# 03__EFR32_Signal_Assignments.net
KiCad netlist of a schematic drawn in Altium Designer
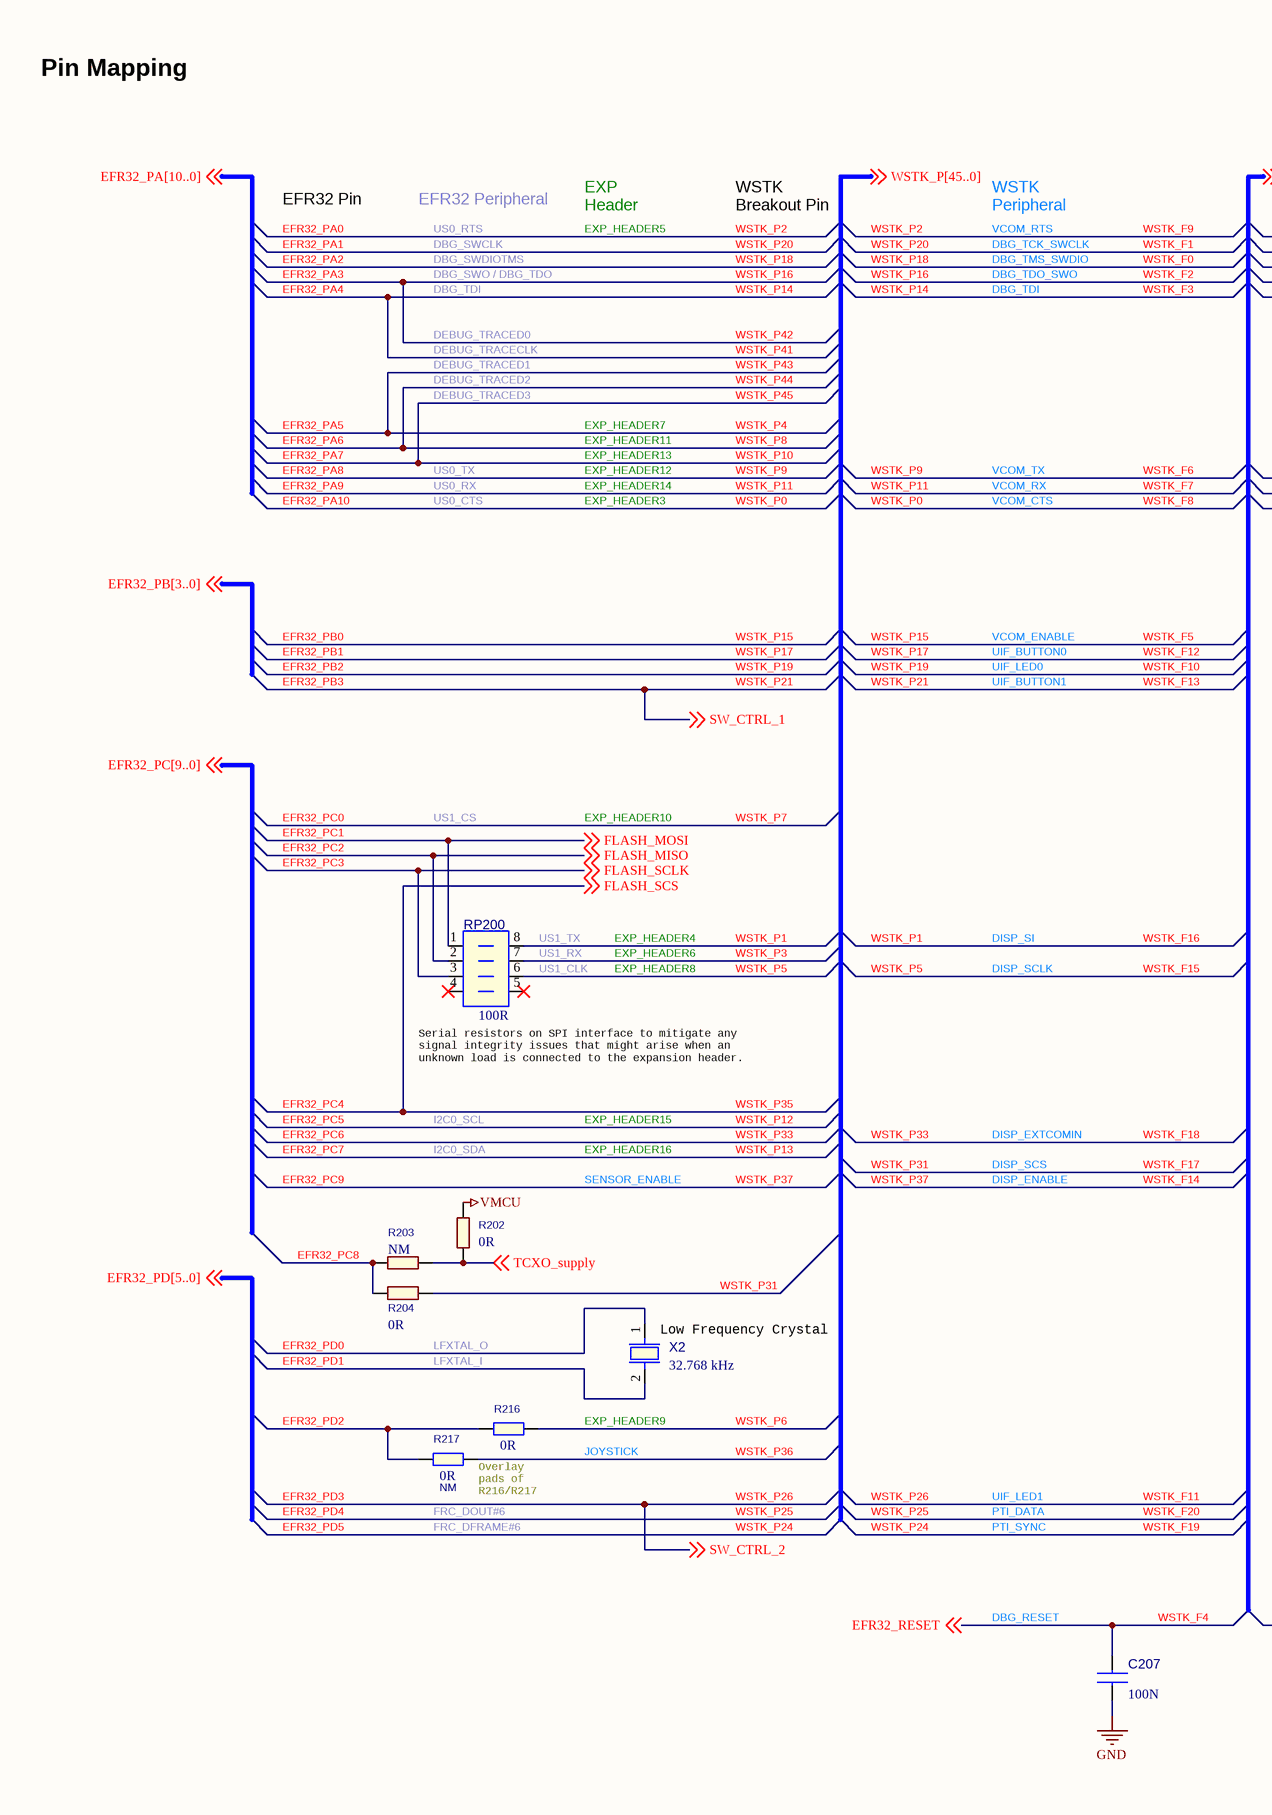
[diagram p0: 03_ EFR32 Signal Assignments.SchDoc, left]
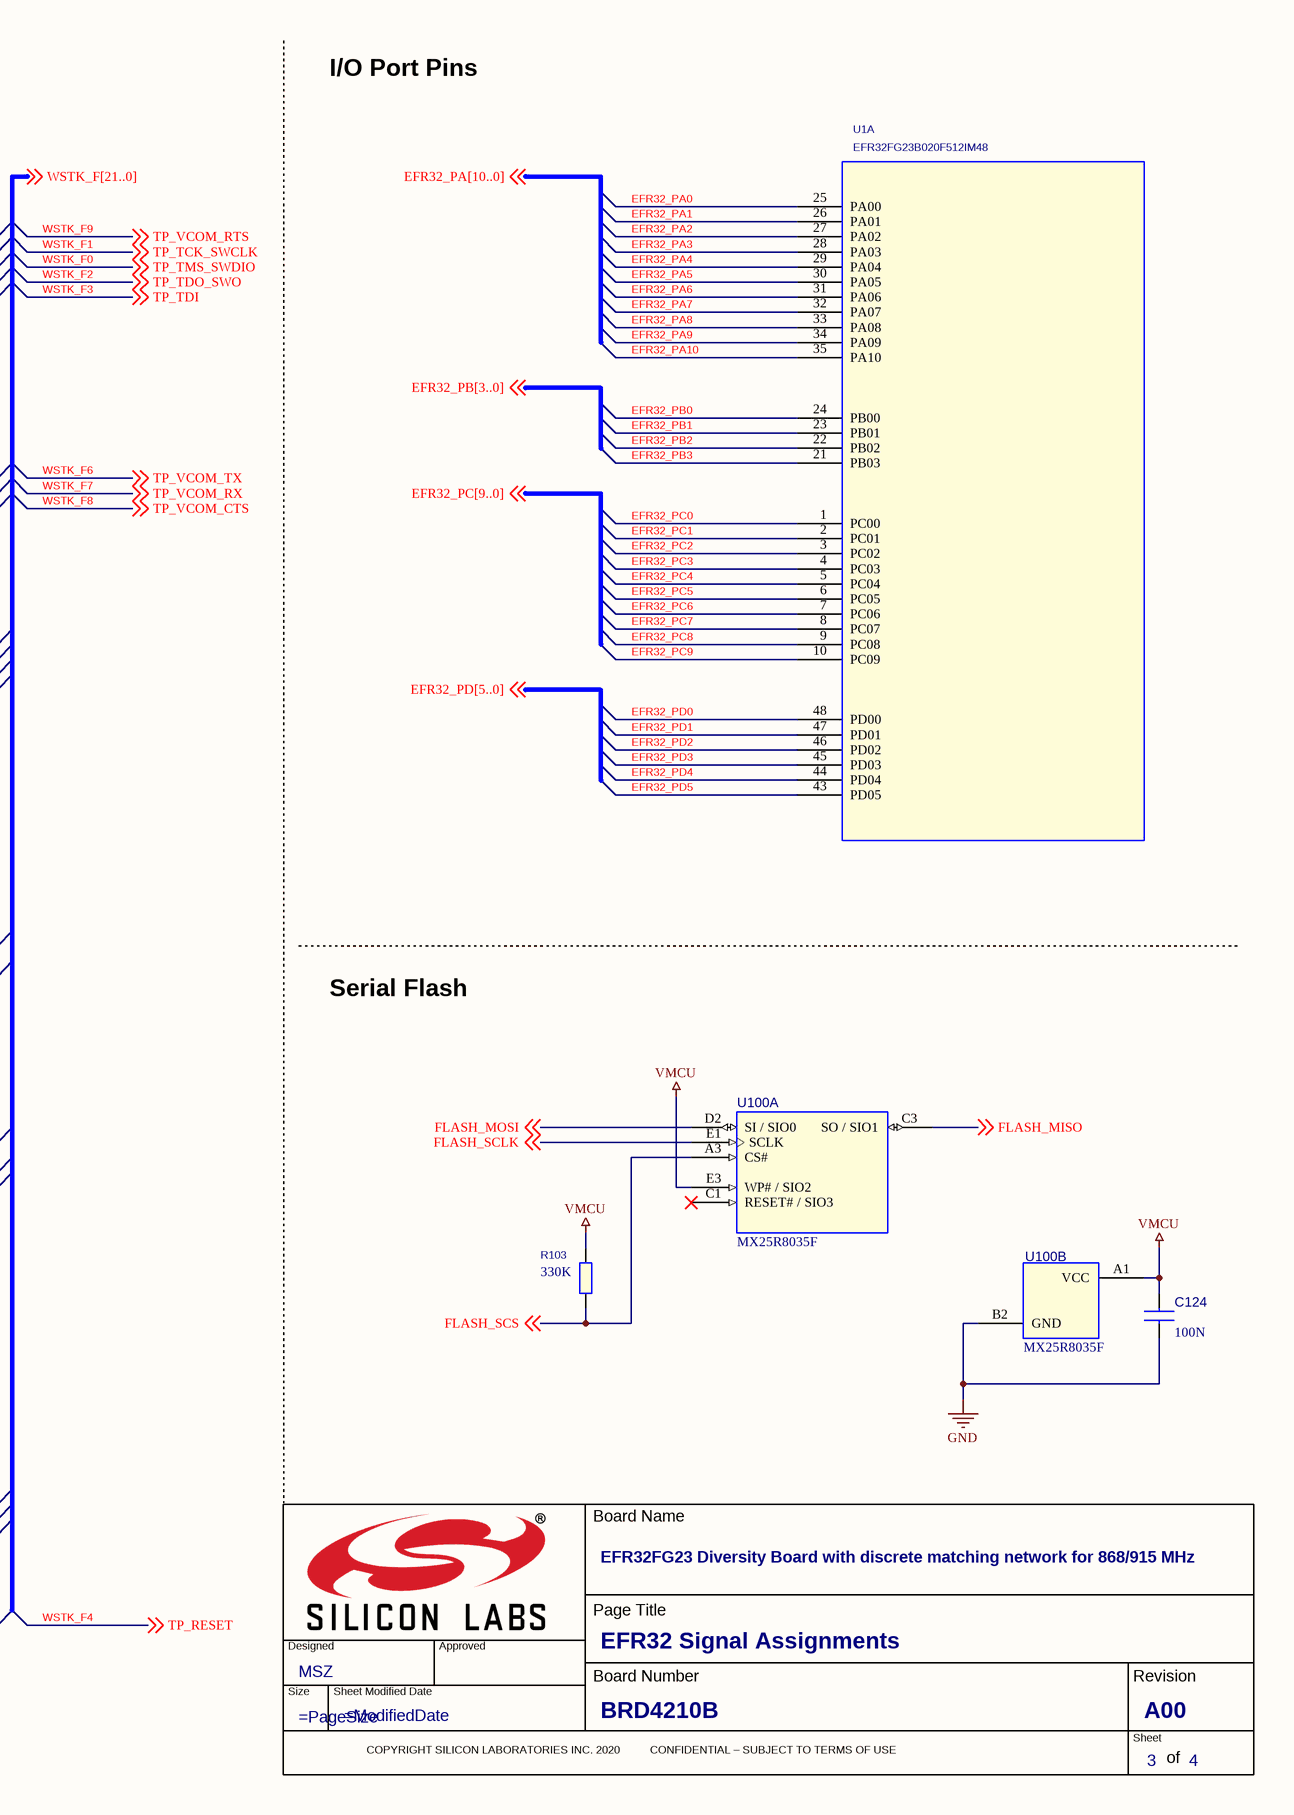
[diagram p1: 03_ EFR32 Signal Assignments.SchDoc, right]

(export (version "E")
  (design (tool "Eeschema 10.0.6"))
  (components
    (comp (ref "C124")
      (value "100N")
      (footprint "C0201_L")
      (fields (field (name "TOLERANCE") "20%"))
      (libsource (lib "*") (part "C0201"))
    )
    (comp (ref "C207")
      (value "100N")
      (footprint "C0201_L")
      (fields (field (name "TOLERANCE") "20%"))
      (libsource (lib "*") (part "C0201"))
    )
    (comp (ref "R103") (value "330K") (footprint "R0201_L") (libsource (lib "*") (part "R0201")))
    (comp (ref "R202") (value "0R") (footprint "R0201_L") (libsource (lib "") (part "R0201_1")))
    (comp (ref "R203") (value "NM") (footprint "R0201_L") (libsource (lib "BRD4210A_Library") (part "R0201")))
    (comp (ref "R204") (value "0R") (footprint "R0201_L") (libsource (lib "BRD4210A_Library") (part "R0201")))
    (comp (ref "R216") (value "0R") (footprint "R0402_L") (libsource (lib "*") (part "R0402")))
    (comp (ref "R217")
      (value "0R")
      (footprint "R0402_L")
      (fields (field (name "NOT MOUNTED") "NM"))
      (libsource (lib "*") (part "R0402"))
    )
    (comp (ref "RP200")
      (value "100R")
      (footprint "RES_MNR04-8")
      (fields (field (name "MFG") "ROHM"))
      (libsource (lib "*") (part "MNR04M0APJ101"))
    )
    (comp (ref "U1")
      (value "EFR32FG23B020F512IM48")
      (footprint "QFN48_M040_6.0X6.0_EP_SL")
      (fields (field (name "MFG") "Silicon Labs"))
      (libsource (lib "*") (part "EFR32xG23_QFN48"))
    )
    (comp (ref "U100")
      (value "MX25R8035F")
      (footprint "BGA8_M040_1.24x1.75_WLCSP")
      (fields (field (name "MFG") "Macronix"))
      (libsource (lib "*") (part "MX25R8035"))
    )
    (comp (ref "X2")
      (value "32.768 kHz")
      (footprint "X_MCS_CM8V-T1A")
      (fields (field (name "MFG") "Micro Crystal AG"))
      (libsource (lib "*") (part "CM8V-T1A"))
    )
  )
  (nets
    (net (code "3") (name "EFR32_PC8") (class "Default")
      (node (ref "R203") (pin "2") (pinfunction "2_2") (pintype "passive"))
      (node (ref "R204") (pin "2") (pinfunction "2_2") (pintype "passive"))
      (node (ref "U1") (pin "9") (pinfunction "PC08_9") (pintype "passive"))
    )
    (net (code "5") (name "EFR32_PD0") (class "Default")
      (node (ref "U1") (pin "48") (pinfunction "PD00_48") (pintype "passive"))
      (node (ref "X2") (pin "1") (pinfunction "1_1") (pintype "passive"))
    )
    (net (code "6") (name "EFR32_PD1") (class "Default")
      (node (ref "U1") (pin "47") (pinfunction "PD01_47") (pintype "passive"))
      (node (ref "X2") (pin "2") (pinfunction "2_2") (pintype "passive"))
    )
    (net (code "7") (name "EFR32_PD2") (class "Default")
      (node (ref "R216") (pin "1") (pinfunction "1_1") (pintype "passive"))
      (node (ref "R217") (pin "1") (pinfunction "1_1") (pintype "passive"))
      (node (ref "U1") (pin "46") (pinfunction "PD02_46") (pintype "passive"))
    )
    (net (code "9") (name "EFR32_RESET") (class "Default")
      (node (ref "C207") (pin "1") (pinfunction "1_1") (pintype "passive"))
    )
    (net (code "10") (name "FLASH_MISO") (class "Default")
      (node (ref "RP200") (pin "2") (pinfunction "R12_2") (pintype "passive"))
      (node (ref "U1") (pin "3") (pinfunction "PC02_3") (pintype "passive"))
      (node (ref "U100") (pin "C3") (pinfunction "SO_/_SIO1_C3") (pintype "bidirectional"))
    )
    (net (code "11") (name "FLASH_MOSI") (class "Default")
      (node (ref "RP200") (pin "1") (pinfunction "R11_1") (pintype "passive"))
      (node (ref "U1") (pin "2") (pinfunction "PC01_2") (pintype "passive"))
      (node (ref "U100") (pin "D2") (pinfunction "SI_/_SIO0_D2") (pintype "bidirectional"))
    )
    (net (code "12") (name "FLASH_SCLK") (class "Default")
      (node (ref "RP200") (pin "3") (pinfunction "R13_3") (pintype "passive"))
      (node (ref "U1") (pin "4") (pinfunction "PC03_4") (pintype "passive"))
      (node (ref "U100") (pin "E1") (pinfunction "SCLK_E1") (pintype "input"))
    )
    (net (code "13") (name "FLASH_SCS") (class "Default")
      (node (ref "R103") (pin "1") (pinfunction "1_1") (pintype "passive"))
      (node (ref "U1") (pin "5") (pinfunction "PC04_5") (pintype "passive"))
      (node (ref "U100") (pin "A3") (pinfunction "CS#_A3") (pintype "input"))
    )
    (net (code "14") (name "GND") (class "Default")
      (node (ref "C124") (pin "2") (pinfunction "2_2") (pintype "passive"))
      (node (ref "C207") (pin "2") (pinfunction "2_2") (pintype "passive"))
      (node (ref "U100") (pin "B2") (pinfunction "GND_B2") (pintype "power_in"))
    )
    (net (code "15") (name "SW_CTRL_1") (class "Default")
      (node (ref "U1") (pin "21") (pinfunction "PB03_21") (pintype "passive"))
    )
    (net (code "16") (name "SW_CTRL_2") (class "Default")
      (node (ref "U1") (pin "45") (pinfunction "PD03_45") (pintype "passive"))
    )
    (net (code "17") (name "TCXO_supply") (class "Default")
      (node (ref "R202") (pin "1") (pinfunction "1_1") (pintype "passive"))
      (node (ref "R203") (pin "1") (pinfunction "1_1") (pintype "passive"))
    )
    (net (code "18") (name "TP_TCK_SWCLK") (class "Default")
      (node (ref "U1") (pin "26") (pinfunction "PA01_26") (pintype "passive"))
    )
    (net (code "19") (name "TP_TDI") (class "Default")
      (node (ref "U1") (pin "29") (pinfunction "PA04_29") (pintype "passive"))
    )
    (net (code "20") (name "TP_TDO_SWO") (class "Default")
      (node (ref "U1") (pin "28") (pinfunction "PA03_28") (pintype "passive"))
    )
    (net (code "21") (name "TP_TMS_SWDIO") (class "Default")
      (node (ref "U1") (pin "27") (pinfunction "PA02_27") (pintype "passive"))
    )
    (net (code "22") (name "TP_VCOM_CTS") (class "Default")
      (node (ref "U1") (pin "35") (pinfunction "PA10_35") (pintype "passive"))
    )
    (net (code "23") (name "TP_VCOM_RTS") (class "Default")
      (node (ref "U1") (pin "25") (pinfunction "PA00_25") (pintype "passive"))
    )
    (net (code "24") (name "TP_VCOM_RX") (class "Default")
      (node (ref "U1") (pin "34") (pinfunction "PA09_34") (pintype "passive"))
    )
    (net (code "25") (name "TP_VCOM_TX") (class "Default")
      (node (ref "U1") (pin "33") (pinfunction "PA08_33") (pintype "passive"))
    )
    (net (code "26") (name "VMCU") (class "Default")
      (node (ref "C124") (pin "1") (pinfunction "1_1") (pintype "passive"))
      (node (ref "R103") (pin "2") (pinfunction "2_2") (pintype "passive"))
      (node (ref "R202") (pin "2") (pinfunction "2_2") (pintype "passive"))
      (node (ref "U100") (pin "A1") (pinfunction "VCC_A1") (pintype "power_in"))
      (node (ref "U100") (pin "E3") (pinfunction "WP#_/_SIO2_E3") (pintype "input"))
    )
    (net (code "27") (name "WSTK_F5") (class "Default")
      (node (ref "U1") (pin "24") (pinfunction "PB00_24") (pintype "passive"))
    )
    (net (code "28") (name "WSTK_F10") (class "Default")
      (node (ref "U1") (pin "22") (pinfunction "PB02_22") (pintype "passive"))
    )
    (net (code "29") (name "WSTK_F12") (class "Default")
      (node (ref "U1") (pin "23") (pinfunction "PB01_23") (pintype "passive"))
    )
    (net (code "30") (name "WSTK_F14") (class "Default")
      (node (ref "U1") (pin "10") (pinfunction "PC09_10") (pintype "passive"))
    )
    (net (code "31") (name "WSTK_F15") (class "Default")
      (node (ref "RP200") (pin "6") (pinfunction "R16_6") (pintype "passive"))
    )
    (net (code "32") (name "WSTK_F16") (class "Default")
      (node (ref "RP200") (pin "8") (pinfunction "R18_8") (pintype "passive"))
    )
    (net (code "33") (name "WSTK_F17") (class "Default")
      (node (ref "R204") (pin "1") (pinfunction "1_1") (pintype "passive"))
    )
    (net (code "34") (name "WSTK_F18") (class "Default")
      (node (ref "U1") (pin "7") (pinfunction "PC06_7") (pintype "passive"))
    )
    (net (code "35") (name "WSTK_F19") (class "Default")
      (node (ref "U1") (pin "43") (pinfunction "PD05_43") (pintype "passive"))
    )
    (net (code "36") (name "WSTK_F20") (class "Default")
      (node (ref "U1") (pin "44") (pinfunction "PD04_44") (pintype "passive"))
    )
    (net (code "38") (name "WSTK_P3") (class "Default")
      (node (ref "RP200") (pin "7") (pinfunction "R17_7") (pintype "passive"))
    )
    (net (code "39") (name "WSTK_P6") (class "Default")
      (node (ref "R216") (pin "2") (pinfunction "2_2") (pintype "passive"))
    )
    (net (code "40") (name "WSTK_P7") (class "Default")
      (node (ref "U1") (pin "1") (pinfunction "PC00_1") (pintype "passive"))
    )
    (net (code "41") (name "WSTK_P8") (class "Default")
      (node (ref "U1") (pin "31") (pinfunction "PA06_31") (pintype "passive"))
    )
    (net (code "42") (name "WSTK_P12") (class "Default")
      (node (ref "U1") (pin "6") (pinfunction "PC05_6") (pintype "passive"))
    )
    (net (code "43") (name "WSTK_P13") (class "Default")
      (node (ref "U1") (pin "8") (pinfunction "PC07_8") (pintype "passive"))
    )
    (net (code "44") (name "WSTK_P36") (class "Default")
      (node (ref "R217") (pin "2") (pinfunction "2_2") (pintype "passive"))
    )
    (net (code "45") (name "WSTK_P43") (class "Default")
      (node (ref "U1") (pin "30") (pinfunction "PA05_30") (pintype "passive"))
    )
    (net (code "46") (name "WSTK_P45") (class "Default")
      (node (ref "U1") (pin "32") (pinfunction "PA07_32") (pintype "passive"))
    )
    (net (code "48") (name "unconnected-(RP200-R14-Pad4)") (class "Default")
      (node (ref "RP200") (pin "4") (pinfunction "R14_4") (pintype "passive+no_connect"))
    )
    (net (code "49") (name "unconnected-(RP200-R15-Pad5)") (class "Default")
      (node (ref "RP200") (pin "5") (pinfunction "R15_5") (pintype "passive+no_connect"))
    )
    (net (code "50") (name "unconnected-(U100A-RESET#_{slash}_SIO3-PadC1)") (class "Default")
      (node (ref "U100") (pin "C1") (pinfunction "RESET#_/_SIO3_C1") (pintype "input+no_connect"))
    )
  )
)
